# DimmerV1_2.net
KiCad netlist of a schematic drawn in EAGLE
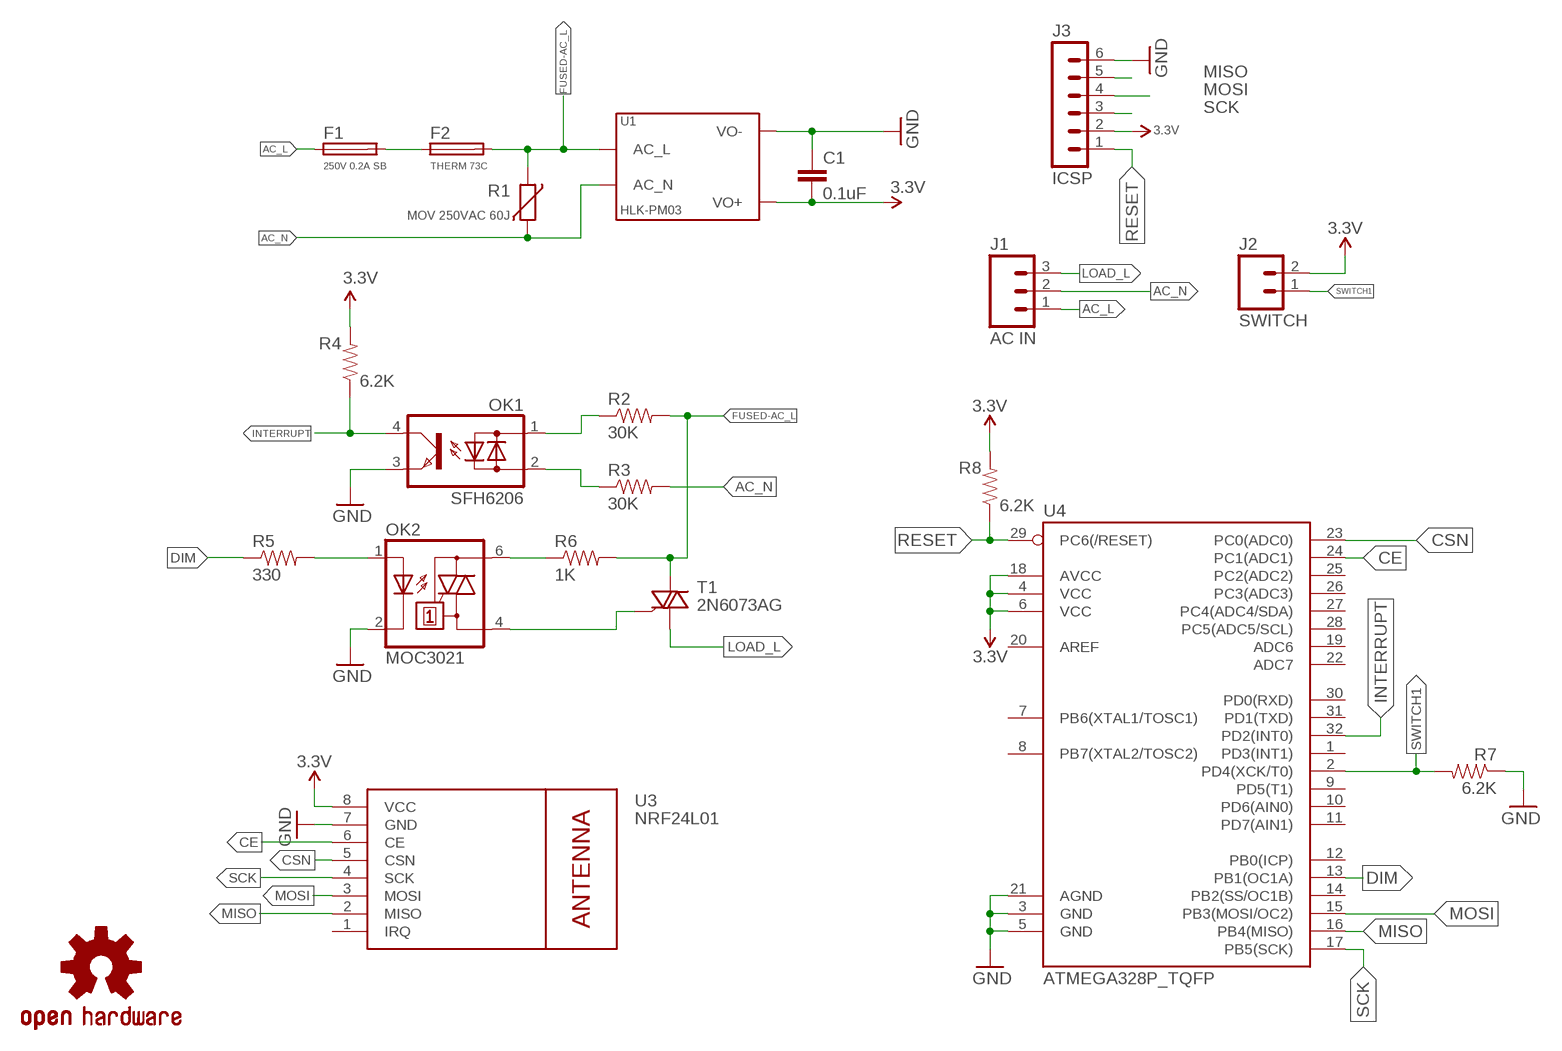
[diagram p0: schematic, sheet 1]

(export (version "E")
  (design (tool "Eeschema 10.0.6"))
  (components
    (comp (ref "C1")
      (value "0.1uF")
      (footprint "eagle-import:0805")
      (libsource (lib "eagle-import") (part "CAP0805"))
    )
    (comp (ref "F1")
      (value "250V 0.2A SB")
      (footprint "eagle-import:TR5")
      (libsource (lib "eagle-import") (part "TR5"))
    )
    (comp (ref "F2")
      (value "THERM 73C")
      (footprint "eagle-import:TE5")
      (libsource (lib "eagle-import") (part "TE5"))
    )
    (comp (ref "J1")
      (value "AC IN")
      (footprint "eagle-import:SCREWTERMINAL-5MM-3")
      (libsource (lib "eagle-import") (part "M03-SCREW-5MM"))
    )
    (comp (ref "J2")
      (value "SWITCH")
      (footprint "eagle-import:SCREWTERMINAL-5MM-2")
      (libsource (lib "eagle-import") (part "M025MM"))
    )
    (comp (ref "J3")
      (value "ICSP")
      (footprint "eagle-import:06X1-PTH")
      (libsource (lib "eagle-import") (part "HEADER-06X1?-MALE"))
    )
    (comp (ref "LOGO1")
      (value "OSHW-LOGOM")
      (footprint "eagle-import:OSHW-LOGO-M")
      (libsource (lib "eagle-import") (part "OSHW-LOGOM"))
    )
    (comp (ref "OK1")
      (value "SFH6206")
      (footprint "eagle-import:DIL4-SMD")
      (fields (field (name "MF") "VISHAY/TELEFUNKEN") (field (name "MPN") "SFH6206-3"))
      (libsource (lib "eagle-import") (part "SFH6206"))
    )
    (comp (ref "OK2")
      (value "MOC3021")
      (footprint "eagle-import:DIL6-SMD")
      (fields (field (name "MF") "FAIRCHILD SEMICONDUCTOR") (field (name "MPN") "MOC3043SM"))
      (libsource (lib "eagle-import") (part "MOC30S43"))
    )
    (comp (ref "R1")
      (value "MOV 250VAC 60J")
      (footprint "eagle-import:S05K11")
      (libsource (lib "eagle-import") (part "VARISTORS05K11"))
    )
    (comp (ref "R2")
      (value "30K")
      (footprint "eagle-import:0805")
      (libsource (lib "eagle-import") (part "SparkFun-Resistors_RESISTOR0805-RES"))
    )
    (comp (ref "R3")
      (value "30K")
      (footprint "eagle-import:0805")
      (libsource (lib "eagle-import") (part "SparkFun-Resistors_RESISTOR0805-RES"))
    )
    (comp (ref "R4")
      (value "6.2K")
      (footprint "eagle-import:0805")
      (libsource (lib "eagle-import") (part "RESISTOR0805-RES"))
    )
    (comp (ref "R5")
      (value "330")
      (footprint "eagle-import:0805")
      (libsource (lib "eagle-import") (part "SparkFun-Resistors_RESISTOR0805-RES"))
    )
    (comp (ref "R6")
      (value "1K")
      (footprint "eagle-import:0805")
      (libsource (lib "eagle-import") (part "SparkFun-Resistors_RESISTOR0805-RES"))
    )
    (comp (ref "R7")
      (value "6.2K")
      (footprint "eagle-import:0805")
      (libsource (lib "eagle-import") (part "RESISTOR0805-RES"))
    )
    (comp (ref "R8")
      (value "6.2K")
      (footprint "eagle-import:0805")
      (libsource (lib "eagle-import") (part "RESISTOR0805-RES"))
    )
    (comp (ref "T1")
      (value "2N6073AG")
      (footprint "eagle-import:TO220DS")
      (libsource (lib "eagle-import") (part "TIC225S"))
    )
    (comp (ref "U1")
      (value "HLK-PM03")
      (footprint "eagle-import:HLK-PM03")
      (libsource (lib "eagle-import") (part "HLK-PM03"))
    )
    (comp (ref "U3")
      (value "NRF24L01")
      (footprint "eagle-import:WIRELESS-NRF24L01-SMD")
      (libsource (lib "eagle-import") (part "WIRELESS-NRF24L01SMD"))
    )
    (comp (ref "U4")
      (value "ATMEGA328P_TQFP")
      (footprint "eagle-import:TQFP32-08")
      (libsource (lib "eagle-import") (part "ATMEGA328P_TQFP"))
    )
  )
  (nets
    (net (code "1") (name "3.3V") (class "Default")
      (node (ref "C1") (pin "2") (pinfunction "2_2") (pintype "passive"))
      (node (ref "J2") (pin "2") (pinfunction "2_2") (pintype "passive"))
      (node (ref "J3") (pin "2") (pinfunction "2_2") (pintype "passive"))
      (node (ref "R4") (pin "2") (pinfunction "2_2") (pintype "passive"))
      (node (ref "R8") (pin "2") (pinfunction "2_2") (pintype "passive"))
      (node (ref "U1") (pin "VO+") (pinfunction "VO+_VO+") (pintype "output"))
      (node (ref "U3") (pin "8") (pinfunction "VCC_8") (pintype "power_in"))
      (node (ref "U4") (pin "18") (pinfunction "AVCC_18") (pintype "bidirectional"))
      (node (ref "U4") (pin "4") (pinfunction "VCC_4") (pintype "bidirectional"))
      (node (ref "U4") (pin "6") (pinfunction "VCC_6") (pintype "bidirectional"))
    )
    (net (code "2") (name "AC_L") (class "Default")
      (node (ref "F1") (pin "1") (pinfunction "1_1") (pintype "passive"))
      (node (ref "J1") (pin "1") (pinfunction "1_1") (pintype "passive"))
    )
    (net (code "3") (name "AC_N") (class "Default")
      (node (ref "J1") (pin "2") (pinfunction "2_2") (pintype "passive"))
      (node (ref "R1") (pin "2") (pinfunction "2_2") (pintype "passive"))
      (node (ref "R3") (pin "2") (pinfunction "2_2") (pintype "passive"))
      (node (ref "U1") (pin "AC_N") (pinfunction "AC_N_AC_N") (pintype "input"))
    )
    (net (code "4") (name "CE") (class "Default")
      (node (ref "U3") (pin "6") (pinfunction "CE_6") (pintype "bidirectional"))
      (node (ref "U4") (pin "24") (pinfunction "PC1(ADC1)_24") (pintype "bidirectional"))
    )
    (net (code "5") (name "CSN") (class "Default")
      (node (ref "U3") (pin "5") (pinfunction "CSN_5") (pintype "bidirectional"))
      (node (ref "U4") (pin "23") (pinfunction "PC0(ADC0)_23") (pintype "bidirectional"))
    )
    (net (code "6") (name "DIM") (class "Default")
      (node (ref "R5") (pin "1") (pinfunction "1_1") (pintype "passive"))
      (node (ref "U4") (pin "13") (pinfunction "PB1(OC1A)_13") (pintype "bidirectional"))
    )
    (net (code "7") (name "FUSED-AC_L") (class "Default")
      (node (ref "F2") (pin "2") (pinfunction "2_2") (pintype "passive"))
      (node (ref "R1") (pin "1") (pinfunction "1_1") (pintype "passive"))
      (node (ref "R2") (pin "2") (pinfunction "2_2") (pintype "passive"))
      (node (ref "R6") (pin "2") (pinfunction "2_2") (pintype "passive"))
      (node (ref "T1") (pin "A2") (pinfunction "A2_A2") (pintype "passive"))
      (node (ref "U1") (pin "AC_L") (pinfunction "AC_L_AC_L") (pintype "input"))
    )
    (net (code "8") (name "GND") (class "Default")
      (node (ref "C1") (pin "1") (pinfunction "1_1") (pintype "passive"))
      (node (ref "J3") (pin "6") (pinfunction "6_6") (pintype "passive"))
      (node (ref "OK1") (pin "3") (pinfunction "E_3") (pintype "passive"))
      (node (ref "OK2") (pin "2") (pinfunction "C_2") (pintype "passive"))
      (node (ref "R7") (pin "1") (pinfunction "1_1") (pintype "passive"))
      (node (ref "U1") (pin "VO-") (pinfunction "VO-_VO-") (pintype "output"))
      (node (ref "U3") (pin "7") (pinfunction "GND_7") (pintype "power_in"))
      (node (ref "U4") (pin "21") (pinfunction "AGND_21") (pintype "bidirectional"))
      (node (ref "U4") (pin "3") (pinfunction "GND_3") (pintype "bidirectional"))
      (node (ref "U4") (pin "5") (pinfunction "GND_5") (pintype "bidirectional"))
    )
    (net (code "9") (name "INTERRUPT") (class "Default")
      (node (ref "OK1") (pin "4") (pinfunction "C_4") (pintype "passive"))
      (node (ref "R4") (pin "1") (pinfunction "1_1") (pintype "passive"))
      (node (ref "U4") (pin "32") (pinfunction "PD2(INT0)_32") (pintype "bidirectional"))
    )
    (net (code "10") (name "LOAD_L") (class "Default")
      (node (ref "J1") (pin "3") (pinfunction "3_3") (pintype "passive"))
      (node (ref "T1") (pin "A1") (pinfunction "A1_A1") (pintype "passive"))
    )
    (net (code "11") (name "MISO") (class "Default")
      (node (ref "J3") (pin "5") (pinfunction "5_5") (pintype "passive"))
      (node (ref "U3") (pin "2") (pinfunction "MISO_2") (pintype "bidirectional"))
      (node (ref "U4") (pin "16") (pinfunction "PB4(MISO)_16") (pintype "bidirectional"))
    )
    (net (code "12") (name "MOSI") (class "Default")
      (node (ref "J3") (pin "4") (pinfunction "4_4") (pintype "passive"))
      (node (ref "U3") (pin "3") (pinfunction "MOSI_3") (pintype "bidirectional"))
      (node (ref "U4") (pin "15") (pinfunction "PB3(MOSI/OC2)_15") (pintype "bidirectional"))
    )
    (net (code "13") (name "Net-(F1-Pad2)") (class "Default")
      (node (ref "F1") (pin "2") (pinfunction "2_2") (pintype "passive"))
      (node (ref "F2") (pin "1") (pinfunction "1_1") (pintype "passive"))
    )
    (net (code "14") (name "Net-(OK1-AC1)") (class "Default")
      (node (ref "OK1") (pin "1") (pinfunction "AC1_1") (pintype "passive"))
      (node (ref "R2") (pin "1") (pinfunction "1_1") (pintype "passive"))
    )
    (net (code "15") (name "Net-(OK1-AC2)") (class "Default")
      (node (ref "OK1") (pin "2") (pinfunction "AC2_2") (pintype "passive"))
      (node (ref "R3") (pin "1") (pinfunction "1_1") (pintype "passive"))
    )
    (net (code "16") (name "Net-(OK2-A)") (class "Default")
      (node (ref "OK2") (pin "1") (pinfunction "A_1") (pintype "passive"))
      (node (ref "R5") (pin "2") (pinfunction "2_2") (pintype "passive"))
    )
    (net (code "17") (name "Net-(OK2-A1)") (class "Default")
      (node (ref "OK2") (pin "4") (pinfunction "A1_4") (pintype "passive"))
      (node (ref "T1") (pin "G") (pinfunction "G_G") (pintype "passive"))
    )
    (net (code "18") (name "Net-(OK2-A2)") (class "Default")
      (node (ref "OK2") (pin "6") (pinfunction "A2_6") (pintype "passive"))
      (node (ref "R6") (pin "1") (pinfunction "1_1") (pintype "passive"))
    )
    (net (code "19") (name "RESET") (class "Default")
      (node (ref "J3") (pin "1") (pinfunction "1_1") (pintype "passive"))
      (node (ref "R8") (pin "1") (pinfunction "1_1") (pintype "passive"))
      (node (ref "U4") (pin "29") (pinfunction "PC6(/RESET)_29") (pintype "bidirectional"))
    )
    (net (code "20") (name "SCK") (class "Default")
      (node (ref "J3") (pin "3") (pinfunction "3_3") (pintype "passive"))
      (node (ref "U3") (pin "4") (pinfunction "SCK_4") (pintype "bidirectional"))
      (node (ref "U4") (pin "17") (pinfunction "PB5(SCK)_17") (pintype "bidirectional"))
    )
    (net (code "21") (name "SWITCH1") (class "Default")
      (node (ref "J2") (pin "1") (pinfunction "1_1") (pintype "passive"))
      (node (ref "R7") (pin "2") (pinfunction "2_2") (pintype "passive"))
      (node (ref "U4") (pin "2") (pinfunction "PD4(XCK/T0)_2") (pintype "bidirectional"))
    )
    (net (code "22") (name "unconnected-(U3-IRQ-Pad1)") (class "Default")
      (node (ref "U3") (pin "1") (pinfunction "IRQ_1") (pintype "bidirectional"))
    )
    (net (code "23") (name "unconnected-(U4-ADC6-Pad19)") (class "Default")
      (node (ref "U4") (pin "19") (pinfunction "ADC6_19") (pintype "bidirectional"))
    )
    (net (code "24") (name "unconnected-(U4-ADC7-Pad22)") (class "Default")
      (node (ref "U4") (pin "22") (pinfunction "ADC7_22") (pintype "bidirectional"))
    )
    (net (code "25") (name "unconnected-(U4-AREF-Pad20)") (class "Default")
      (node (ref "U4") (pin "20") (pinfunction "AREF_20") (pintype "bidirectional"))
    )
    (net (code "26") (name "unconnected-(U4-PB0(ICP)-Pad12)") (class "Default")
      (node (ref "U4") (pin "12") (pinfunction "PB0(ICP)_12") (pintype "bidirectional"))
    )
    (net (code "27") (name "unconnected-(U4-PB2(SS{slash}OC1B)-Pad14)") (class "Default")
      (node (ref "U4") (pin "14") (pinfunction "PB2(SS/OC1B)_14") (pintype "bidirectional"))
    )
    (net (code "28") (name "unconnected-(U4-PB6(XTAL1{slash}TOSC1)-Pad7)") (class "Default")
      (node (ref "U4") (pin "7") (pinfunction "PB6(XTAL1/TOSC1)_7") (pintype "bidirectional"))
    )
    (net (code "29") (name "unconnected-(U4-PB7(XTAL2{slash}TOSC2)-Pad8)") (class "Default")
      (node (ref "U4") (pin "8") (pinfunction "PB7(XTAL2/TOSC2)_8") (pintype "bidirectional"))
    )
    (net (code "30") (name "unconnected-(U4-PC2(ADC2)-Pad25)") (class "Default")
      (node (ref "U4") (pin "25") (pinfunction "PC2(ADC2)_25") (pintype "bidirectional"))
    )
    (net (code "31") (name "unconnected-(U4-PC3(ADC3)-Pad26)") (class "Default")
      (node (ref "U4") (pin "26") (pinfunction "PC3(ADC3)_26") (pintype "bidirectional"))
    )
    (net (code "32") (name "unconnected-(U4-PC4(ADC4{slash}SDA)-Pad27)") (class "Default")
      (node (ref "U4") (pin "27") (pinfunction "PC4(ADC4/SDA)_27") (pintype "bidirectional"))
    )
    (net (code "33") (name "unconnected-(U4-PC5(ADC5{slash}SCL)-Pad28)") (class "Default")
      (node (ref "U4") (pin "28") (pinfunction "PC5(ADC5/SCL)_28") (pintype "bidirectional"))
    )
    (net (code "34") (name "unconnected-(U4-PD0(RXD)-Pad30)") (class "Default")
      (node (ref "U4") (pin "30") (pinfunction "PD0(RXD)_30") (pintype "bidirectional"))
    )
    (net (code "35") (name "unconnected-(U4-PD1(TXD)-Pad31)") (class "Default")
      (node (ref "U4") (pin "31") (pinfunction "PD1(TXD)_31") (pintype "bidirectional"))
    )
    (net (code "36") (name "unconnected-(U4-PD3(INT1)-Pad1)") (class "Default")
      (node (ref "U4") (pin "1") (pinfunction "PD3(INT1)_1") (pintype "bidirectional"))
    )
    (net (code "37") (name "unconnected-(U4-PD5(T1)-Pad9)") (class "Default")
      (node (ref "U4") (pin "9") (pinfunction "PD5(T1)_9") (pintype "bidirectional"))
    )
    (net (code "38") (name "unconnected-(U4-PD6(AIN0)-Pad10)") (class "Default")
      (node (ref "U4") (pin "10") (pinfunction "PD6(AIN0)_10") (pintype "bidirectional"))
    )
    (net (code "39") (name "unconnected-(U4-PD7(AIN1)-Pad11)") (class "Default")
      (node (ref "U4") (pin "11") (pinfunction "PD7(AIN1)_11") (pintype "bidirectional"))
    )
  )
)
